# 5_spi_memory.net
KiCad netlist of a schematic drawn in Altium Designer
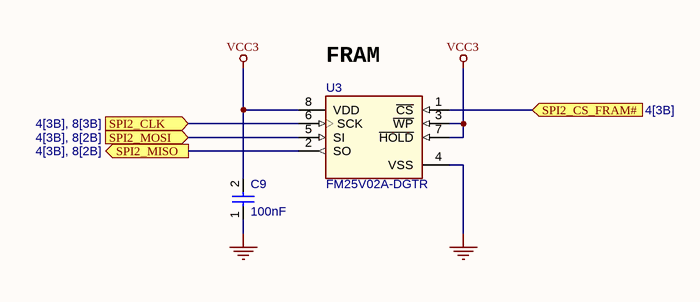
[diagram p0: 5_spi_memory.SchDoc]

(export (version "E")
  (design (tool "Eeschema 10.0.6"))
  (components
    (comp (ref "C9")
      (value "100nF")
      (footprint "CAPC0402(1005)60_L")
      (description "Chip Capacitor, 100nF +/-20%, 10V, 0402, Thickness 0.6 mm")
      (fields (field (name "TOLERANCE") "20%") (field (name "MANUFACTURER") "KEMET"))
      (libsource (lib "Kame_FMU") (part "Capacitor 100nF +/-20% 10V 0402"))
    )
    (comp (ref "U3")
      (value "FM25V02A-DGTR")
      (footprint "SON95P400X75_HS-9N")
      (description "REEL / F-RAM Memory Serial")
      (fields (field (name "MANUFACTURER") "Cypress") (field (name "MANUFACTURER PART NUMBER") "FM25V02A-DG"))
      (libsource (lib "Kame_FMU") (part "FM25V02A-DGTR"))
    )
  )
  (nets
    (net (code "1") (name "/SPI2_CLK") (class "Default")
      (node (ref "U3") (pin "6") (pinfunction "SCK_6") (pintype "input"))
    )
    (net (code "2") (name "/SPI2_CS_FRAM#") (class "Default")
      (node (ref "U3") (pin "1") (pinfunction "~{CS}_1") (pintype "input"))
    )
    (net (code "3") (name "/SPI2_MISO") (class "Default")
      (node (ref "U3") (pin "2") (pinfunction "SO_2") (pintype "output"))
    )
    (net (code "4") (name "/SPI2_MOSI") (class "Default")
      (node (ref "U3") (pin "5") (pinfunction "SI_5") (pintype "input"))
    )
    (net (code "5") (name "GND") (class "Default")
      (node (ref "C9") (pin "1") (pinfunction "1_1") (pintype "passive"))
      (node (ref "U3") (pin "4") (pinfunction "VSS_4") (pintype "power_in"))
    )
    (net (code "6") (name "VCC3") (class "Default")
      (node (ref "C9") (pin "2") (pinfunction "2_2") (pintype "passive"))
      (node (ref "U3") (pin "3") (pinfunction "~{WP}_3") (pintype "input"))
      (node (ref "U3") (pin "7") (pinfunction "~{HOLD}_7") (pintype "input"))
      (node (ref "U3") (pin "8") (pinfunction "VDD_8") (pintype "power_in"))
    )
  )
)
